# NTS2.net
KiCad netlist of a schematic drawn in EAGLE
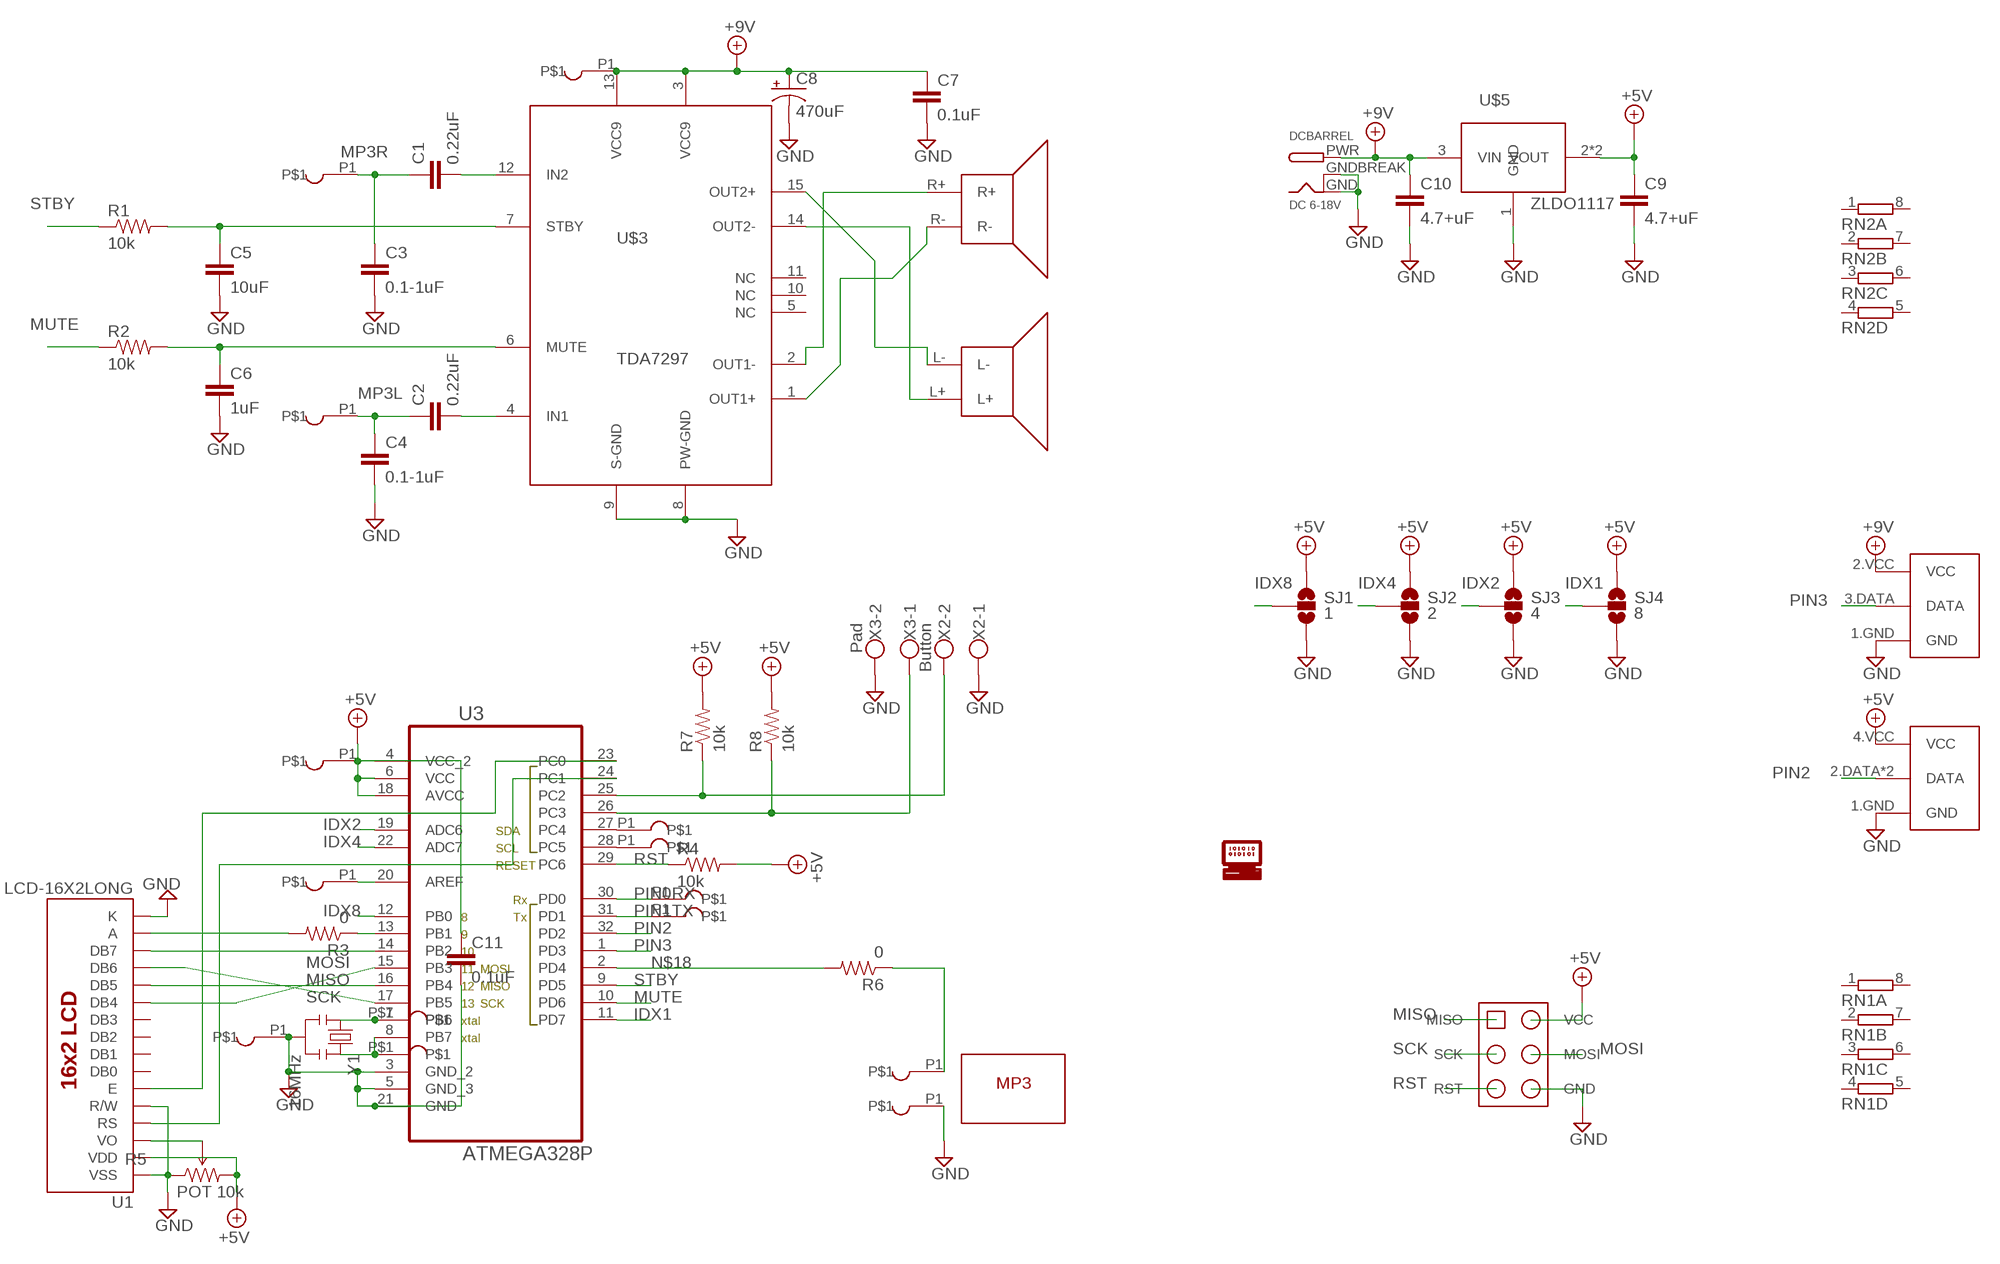
[diagram p0: schematic, sheet 1]

(export (version "E")
  (design (tool "Eeschema 10.0.6"))
  (components
    (comp (ref "AREF")
      (value "AREF")
      (footprint "eagle-import:JMP1")
      (libsource (lib "eagle-import") (part "PROTO-HOLENOSILK"))
    )
    (comp (ref "C1")
      (value "0.22uF")
      (footprint "eagle-import:0805-XL")
      (libsource (lib "eagle-import") (part "CAP0805-XL"))
    )
    (comp (ref "C2")
      (value "0.22uF")
      (footprint "eagle-import:0805-XL")
      (libsource (lib "eagle-import") (part "CAP0805-XL"))
    )
    (comp (ref "C3")
      (value "0.1-1uF")
      (footprint "eagle-import:0805-XL")
      (libsource (lib "eagle-import") (part "CAP0805-XL"))
    )
    (comp (ref "C4")
      (value "0.1-1uF")
      (footprint "eagle-import:0805-XL")
      (libsource (lib "eagle-import") (part "CAP0805-XL"))
    )
    (comp (ref "C5")
      (value "10uF")
      (footprint "eagle-import:0805-XL")
      (libsource (lib "eagle-import") (part "CAP0805-XL"))
    )
    (comp (ref "C6")
      (value "1uF")
      (footprint "eagle-import:0805-XL")
      (libsource (lib "eagle-import") (part "CAP0805-XL"))
    )
    (comp (ref "C7")
      (value "0.1uF")
      (footprint "eagle-import:0805-XL")
      (libsource (lib "eagle-import") (part "CAP0805-XL"))
    )
    (comp (ref "C8")
      (value "470uF")
      (footprint "eagle-import:CAP-PTH-200-POL-HOR-R-600")
      (libsource (lib "eagle-import") (part "CAP_POLHORR"))
    )
    (comp (ref "C9")
      (value "4.7+uF")
      (footprint "eagle-import:1206")
      (libsource (lib "eagle-import") (part "CAP1206"))
    )
    (comp (ref "C10")
      (value "4.7+uF")
      (footprint "eagle-import:0805-XL")
      (libsource (lib "eagle-import") (part "CAP0805-XL"))
    )
    (comp (ref "C11")
      (value "0.1uF")
      (footprint "eagle-import:0805-XL")
      (libsource (lib "eagle-import") (part "CAP0805-XL"))
    )
    (comp (ref "DCBARREL")
      (value "DC 6-18V")
      (footprint "eagle-import:DCJACK_2MM_PTH")
      (libsource (lib "eagle-import") (part "DCBARRELPTH"))
    )
    (comp (ref "GND")
      (value "GND")
      (footprint "eagle-import:JMP1")
      (libsource (lib "eagle-import") (part "PROTO-HOLENOSILK"))
    )
    (comp (ref "MP3+")
      (value "M+")
      (footprint "eagle-import:JMP1-RECT")
      (libsource (lib "eagle-import") (part "PROTO-HOLESILK-RECT"))
    )
    (comp (ref "MP3-")
      (value "M-")
      (footprint "eagle-import:JMP1-RECT")
      (libsource (lib "eagle-import") (part "PROTO-HOLESILK-RECT"))
    )
    (comp (ref "MP3-L")
      (value "L")
      (footprint "eagle-import:JMP1-RECT")
      (libsource (lib "eagle-import") (part "PROTO-HOLESILK-RECT"))
    )
    (comp (ref "MP3-R")
      (value "R")
      (footprint "eagle-import:JMP1-RECT")
      (libsource (lib "eagle-import") (part "PROTO-HOLESILK-RECT"))
    )
    (comp (ref "PB6")
      (value "PB6")
      (footprint "eagle-import:JMP1-SMD-100")
      (libsource (lib "eagle-import") (part "PROTO-HOLESMD100"))
    )
    (comp (ref "PB7")
      (value "PB7")
      (footprint "eagle-import:JMP1-SMD-100")
      (libsource (lib "eagle-import") (part "PROTO-HOLESMD100"))
    )
    (comp (ref "PC4")
      (value "A4")
      (footprint "eagle-import:JMP1")
      (libsource (lib "eagle-import") (part "PROTO-HOLENOSILK"))
    )
    (comp (ref "PC5")
      (value "A5")
      (footprint "eagle-import:JMP1")
      (libsource (lib "eagle-import") (part "PROTO-HOLENOSILK"))
    )
    (comp (ref "PD0")
      (value "Rx")
      (footprint "eagle-import:JMP1")
      (libsource (lib "eagle-import") (part "PROTO-HOLENOSILK"))
    )
    (comp (ref "PD1")
      (value "Tx")
      (footprint "eagle-import:JMP1")
      (libsource (lib "eagle-import") (part "PROTO-HOLENOSILK"))
    )
    (comp (ref "R1")
      (value "10k")
      (footprint "eagle-import:0805-XL")
      (libsource (lib "eagle-import") (part "RESISTOR0805-XL"))
    )
    (comp (ref "R2")
      (value "10k")
      (footprint "eagle-import:0805-XL")
      (libsource (lib "eagle-import") (part "RESISTOR0805-XL"))
    )
    (comp (ref "R3")
      (value "0")
      (footprint "eagle-import:1206")
      (libsource (lib "eagle-import") (part "RESISTOR1206"))
    )
    (comp (ref "R4")
      (value "10k")
      (footprint "eagle-import:0805-XL")
      (libsource (lib "eagle-import") (part "RESISTOR0805-XL"))
    )
    (comp (ref "R5")
      (value "POT 10k")
      (footprint "eagle-import:TRIM_POT_PTH")
      (libsource (lib "eagle-import") (part "TRIMPOTPTH"))
    )
    (comp (ref "R6")
      (value "0")
      (footprint "eagle-import:1206")
      (libsource (lib "eagle-import") (part "RESISTOR1206"))
    )
    (comp (ref "R7")
      (value "10k")
      (footprint "eagle-import:0805-XL")
      (libsource (lib "eagle-import") (part "RESISTOR0805-XL"))
    )
    (comp (ref "R8")
      (value "10k")
      (footprint "eagle-import:0805-XL")
      (libsource (lib "eagle-import") (part "RESISTOR0805-XL"))
    )
    (comp (ref "RN1")
      (value "4R-NCAT16")
      (footprint "eagle-import:CAT16")
      (libsource (lib "eagle-import") (part "4R-NCAT16"))
    )
    (comp (ref "RN2")
      (value "4R-N0402ARV341")
      (footprint "eagle-import:4X0402ARV341")
      (libsource (lib "eagle-import") (part "4R-N0402ARV341"))
    )
    (comp (ref "SJ1")
      (value "1")
      (footprint "eagle-import:SJ_2_BIN-PTH")
      (libsource (lib "eagle-import") (part "JUMPER_2WAYBIN-PTH"))
    )
    (comp (ref "SJ2")
      (value "2")
      (footprint "eagle-import:SJ_2_BIN-PTH")
      (libsource (lib "eagle-import") (part "JUMPER_2WAYBIN-PTH"))
    )
    (comp (ref "SJ3")
      (value "4")
      (footprint "eagle-import:SJ_2_BIN-PTH")
      (libsource (lib "eagle-import") (part "JUMPER_2WAYBIN-PTH"))
    )
    (comp (ref "SJ4")
      (value "8")
      (footprint "eagle-import:SJ_2_BIN-PTH")
      (libsource (lib "eagle-import") (part "JUMPER_2WAYBIN-PTH"))
    )
    (comp (ref "U$1")
      (value "OUTLINE-MP3-MDM")
      (footprint "eagle-import:OUTLINE-MP3-MDM")
      (libsource (lib "eagle-import") (part "OUTLINE-MP3-MDM"))
    )
    (comp (ref "U$2")
      (value "HEAD-2X3-ISPISP6NLL")
      (footprint "eagle-import:HEADER2X3-PTH-NOLABEL-LONG")
      (libsource (lib "eagle-import") (part "HEAD-2X3-ISPISP6NLL"))
    )
    (comp (ref "U$3")
      (value "TDA7297")
      (footprint "eagle-import:TDA7297")
      (libsource (lib "eagle-import") (part "TDA7297-SINK"))
    )
    (comp (ref "U$4")
      (value "SPEAKERSPTH")
      (footprint "eagle-import:SPEAKER-5105")
      (libsource (lib "eagle-import") (part "SPEAKERSPTH"))
    )
    (comp (ref "U$5")
      (value "ZLDO1117")
      (footprint "eagle-import:SOT223-3-L")
      (libsource (lib "eagle-import") (part "VREGZLDO1117"))
    )
    (comp (ref "U$6")
      (value "RF-TRANSMITTER")
      (footprint "eagle-import:RF-TRANSMIT")
      (libsource (lib "eagle-import") (part "RF-TRANSMITTER"))
    )
    (comp (ref "U$7")
      (value "RF-RECEIVER")
      (footprint "eagle-import:RF-RECEIVER")
      (libsource (lib "eagle-import") (part "RF-RECEIVER"))
    )
    (comp (ref "U$8")
      (value "LOGO_HM512")
      (footprint "eagle-import:LOGO_HM_512")
      (libsource (lib "eagle-import") (part "LOGO_HM512"))
    )
    (comp (ref "U1")
      (value "LCD-16X2LONG")
      (footprint "eagle-import:LCD-16X2-LONG")
      (libsource (lib "eagle-import") (part "LCD-16X2LONG"))
    )
    (comp (ref "U3")
      (value "ATMEGA328P")
      (footprint "eagle-import:QFP80P900X900X120-32N-LD")
      (libsource (lib "eagle-import") (part "ATMEGA328P-AUQFP-LONG-DIA"))
    )
    (comp (ref "VCC")
      (value "VCC")
      (footprint "eagle-import:JMP1")
      (libsource (lib "eagle-import") (part "PROTO-HOLENOSILK"))
    )
    (comp (ref "VIN")
      (value "Vin")
      (footprint "eagle-import:JMP1")
      (libsource (lib "eagle-import") (part "PROTO-HOLENOSILK"))
    )
    (comp (ref "X2")
      (value "Button")
      (footprint "eagle-import:CON-SCREW2")
      (fields (field (name "MPN") "237-102"))
      (libsource (lib "eagle-import") (part "CON-SCREW2"))
    )
    (comp (ref "X3")
      (value "Pad")
      (footprint "eagle-import:CON-SCREW2")
      (fields (field (name "MPN") "237-102"))
      (libsource (lib "eagle-import") (part "CON-SCREW2"))
    )
    (comp (ref "Y1")
      (value "16MHz")
      (footprint "eagle-import:SMD-RESONATOR-320-130-PRQC")
      (libsource (lib "eagle-import") (part "RESONATOR8MHZ"))
    )
  )
  (nets
    (net (code "1") (name "+5V") (class "Default")
      (node (ref "C11") (pin "1") (pinfunction "1_1") (pintype "passive"))
      (node (ref "C9") (pin "1") (pinfunction "1_1") (pintype "passive"))
      (node (ref "R4") (pin "2") (pinfunction "2_2") (pintype "passive"))
      (node (ref "R5") (pin "3") (pinfunction "CW_3") (pintype "passive"))
      (node (ref "R7") (pin "2") (pinfunction "2_2") (pintype "passive"))
      (node (ref "R8") (pin "2") (pinfunction "2_2") (pintype "passive"))
      (node (ref "SJ1") (pin "1") (pinfunction "1_1") (pintype "passive"))
      (node (ref "SJ2") (pin "1") (pinfunction "1_1") (pintype "passive"))
      (node (ref "SJ3") (pin "1") (pinfunction "1_1") (pintype "passive"))
      (node (ref "SJ4") (pin "1") (pinfunction "1_1") (pintype "passive"))
      (node (ref "U$2") (pin "VCC") (pinfunction "VCC_VCC") (pintype "bidirectional"))
      (node (ref "U$5") (pin "2") (pinfunction "VOUT_2") (pintype "power_in"))
      (node (ref "U$5") (pin "4") (pinfunction "VOUT_4") (pintype "power_in"))
      (node (ref "U$7") (pin "4.VCC") (pinfunction "VCC_4.VCC") (pintype "power_in"))
      (node (ref "U1") (pin "2") (pinfunction "VDD_2") (pintype "power_in"))
      (node (ref "U3") (pin "18") (pinfunction "AVCC_18") (pintype "power_in"))
      (node (ref "U3") (pin "4") (pinfunction "VCC_2_4") (pintype "power_in"))
      (node (ref "U3") (pin "6") (pinfunction "VCC_6") (pintype "power_in"))
      (node (ref "VCC") (pin "P1") (pinfunction "P$1_P1") (pintype "bidirectional"))
    )
    (net (code "2") (name "+9V") (class "Default")
      (node (ref "C10") (pin "1") (pinfunction "1_1") (pintype "passive"))
      (node (ref "C7") (pin "1") (pinfunction "1_1") (pintype "passive"))
      (node (ref "C8") (pin "2+") (pinfunction "+_2+") (pintype "passive"))
      (node (ref "DCBARREL") (pin "PWR") (pinfunction "PWR_PWR") (pintype "power_in"))
      (node (ref "U$3") (pin "13") (pinfunction "VCC9_13") (pintype "power_in"))
      (node (ref "U$3") (pin "3") (pinfunction "VCC9_3") (pintype "power_in"))
      (node (ref "U$5") (pin "3") (pinfunction "VIN_3") (pintype "power_in"))
      (node (ref "U$6") (pin "2.VCC") (pinfunction "VCC_2.VCC") (pintype "power_in"))
      (node (ref "VIN") (pin "P1") (pinfunction "P$1_P1") (pintype "bidirectional"))
    )
    (net (code "3") (name "/IDX1") (class "Default")
      (node (ref "SJ4") (pin "2") (pinfunction "2.C_2") (pintype "passive"))
      (node (ref "U3") (pin "11") (pinfunction "PD7_11") (pintype "bidirectional"))
    )
    (net (code "4") (name "/IDX2") (class "Default")
      (node (ref "SJ3") (pin "2") (pinfunction "2.C_2") (pintype "passive"))
      (node (ref "U3") (pin "19") (pinfunction "ADC6_19") (pintype "input"))
    )
    (net (code "5") (name "/IDX4") (class "Default")
      (node (ref "SJ2") (pin "2") (pinfunction "2.C_2") (pintype "passive"))
      (node (ref "U3") (pin "22") (pinfunction "ADC7_22") (pintype "input"))
    )
    (net (code "6") (name "/IDX8") (class "Default")
      (node (ref "SJ1") (pin "2") (pinfunction "2.C_2") (pintype "passive"))
      (node (ref "U3") (pin "12") (pinfunction "PB0_12") (pintype "bidirectional"))
    )
    (net (code "7") (name "/MISO") (class "Default")
      (node (ref "U$2") (pin "MISO") (pinfunction "MISO_MISO") (pintype "bidirectional"))
      (node (ref "U1") (pin "12") (pinfunction "DB5_12") (pintype "bidirectional"))
      (node (ref "U3") (pin "16") (pinfunction "PB4_16") (pintype "bidirectional"))
    )
    (net (code "8") (name "/MOSI") (class "Default")
      (node (ref "U$2") (pin "MOSI") (pinfunction "MOSI_MOSI") (pintype "bidirectional"))
      (node (ref "U1") (pin "11") (pinfunction "DB4_11") (pintype "bidirectional"))
      (node (ref "U3") (pin "15") (pinfunction "PB3_15") (pintype "bidirectional"))
    )
    (net (code "9") (name "/MP3L") (class "Default")
      (node (ref "C2") (pin "1") (pinfunction "1_1") (pintype "passive"))
      (node (ref "C4") (pin "1") (pinfunction "1_1") (pintype "passive"))
      (node (ref "MP3-L") (pin "P1") (pinfunction "P$1_P1") (pintype "bidirectional"))
    )
    (net (code "10") (name "/MP3R") (class "Default")
      (node (ref "C1") (pin "1") (pinfunction "1_1") (pintype "passive"))
      (node (ref "C3") (pin "1") (pinfunction "1_1") (pintype "passive"))
      (node (ref "MP3-R") (pin "P1") (pinfunction "P$1_P1") (pintype "bidirectional"))
    )
    (net (code "11") (name "/MUTE") (class "Default")
      (node (ref "R2") (pin "1") (pinfunction "1_1") (pintype "passive"))
      (node (ref "U3") (pin "10") (pinfunction "PD6_10") (pintype "bidirectional"))
    )
    (net (code "12") (name "/N$18") (class "Default")
      (node (ref "R6") (pin "2") (pinfunction "2_2") (pintype "passive"))
      (node (ref "U3") (pin "2") (pinfunction "PD4_2") (pintype "bidirectional"))
    )
    (net (code "13") (name "/PIN0RX") (class "Default")
      (node (ref "PD0") (pin "P1") (pinfunction "P$1_P1") (pintype "bidirectional"))
      (node (ref "U3") (pin "30") (pinfunction "PD0_30") (pintype "bidirectional"))
    )
    (net (code "14") (name "/PIN1TX") (class "Default")
      (node (ref "PD1") (pin "P1") (pinfunction "P$1_P1") (pintype "bidirectional"))
      (node (ref "U3") (pin "31") (pinfunction "PD1_31") (pintype "bidirectional"))
    )
    (net (code "15") (name "/PIN2") (class "Default")
      (node (ref "U$7") (pin "2.DATA") (pinfunction "DATA_2.DATA") (pintype "output"))
      (node (ref "U$7") (pin "3.DATA") (pinfunction "DATA_3.DATA") (pintype "output"))
      (node (ref "U3") (pin "32") (pinfunction "PD2_32") (pintype "bidirectional"))
    )
    (net (code "16") (name "/PIN3") (class "Default")
      (node (ref "U$6") (pin "3.DATA") (pinfunction "DATA_3.DATA") (pintype "input"))
      (node (ref "U3") (pin "1") (pinfunction "PD3_1") (pintype "bidirectional"))
    )
    (net (code "17") (name "/RST") (class "Default")
      (node (ref "R4") (pin "1") (pinfunction "1_1") (pintype "passive"))
      (node (ref "U$2") (pin "RST") (pinfunction "RST_RST") (pintype "bidirectional"))
      (node (ref "U3") (pin "29") (pinfunction "PC6_29") (pintype "bidirectional"))
    )
    (net (code "18") (name "/SCK") (class "Default")
      (node (ref "U$2") (pin "SCK") (pinfunction "SCK_SCK") (pintype "bidirectional"))
      (node (ref "U1") (pin "13") (pinfunction "DB6_13") (pintype "bidirectional"))
      (node (ref "U3") (pin "17") (pinfunction "PB5_17") (pintype "bidirectional"))
    )
    (net (code "19") (name "/STBY") (class "Default")
      (node (ref "R1") (pin "1") (pinfunction "1_1") (pintype "passive"))
      (node (ref "U3") (pin "9") (pinfunction "PD5_9") (pintype "bidirectional"))
    )
    (net (code "20") (name "GND") (class "Default")
      (node (ref "C10") (pin "2") (pinfunction "2_2") (pintype "passive"))
      (node (ref "C11") (pin "2") (pinfunction "2_2") (pintype "passive"))
      (node (ref "C3") (pin "2") (pinfunction "2_2") (pintype "passive"))
      (node (ref "C4") (pin "2") (pinfunction "2_2") (pintype "passive"))
      (node (ref "C5") (pin "2") (pinfunction "2_2") (pintype "passive"))
      (node (ref "C6") (pin "2") (pinfunction "2_2") (pintype "passive"))
      (node (ref "C7") (pin "2") (pinfunction "2_2") (pintype "passive"))
      (node (ref "C8") (pin "1-") (pinfunction "-_1-") (pintype "passive"))
      (node (ref "C9") (pin "2") (pinfunction "2_2") (pintype "passive"))
      (node (ref "DCBARREL") (pin "GND") (pinfunction "GND_GND") (pintype "power_in"))
      (node (ref "DCBARREL") (pin "GNDBREAK") (pinfunction "GNDBREAK_GNDBREAK") (pintype "power_in"))
      (node (ref "GND") (pin "P1") (pinfunction "P$1_P1") (pintype "bidirectional"))
      (node (ref "MP3-") (pin "P1") (pinfunction "P$1_P1") (pintype "bidirectional"))
      (node (ref "R5") (pin "1") (pinfunction "CCW_1") (pintype "passive"))
      (node (ref "SJ1") (pin "3") (pinfunction "3_3") (pintype "passive"))
      (node (ref "SJ2") (pin "3") (pinfunction "3_3") (pintype "passive"))
      (node (ref "SJ3") (pin "3") (pinfunction "3_3") (pintype "passive"))
      (node (ref "SJ4") (pin "3") (pinfunction "3_3") (pintype "passive"))
      (node (ref "U$2") (pin "GND") (pinfunction "GND_GND") (pintype "bidirectional"))
      (node (ref "U$3") (pin "8") (pinfunction "PW-GND_8") (pintype "power_in"))
      (node (ref "U$3") (pin "9") (pinfunction "S-GND_9") (pintype "power_in"))
      (node (ref "U$5") (pin "1") (pinfunction "GND_1") (pintype "power_in"))
      (node (ref "U$6") (pin "1.GND") (pinfunction "GND_1.GND") (pintype "power_in"))
      (node (ref "U$7") (pin "1.GND") (pinfunction "GND_1.GND") (pintype "power_in"))
      (node (ref "U1") (pin "1") (pinfunction "VSS_1") (pintype "power_in"))
      (node (ref "U1") (pin "16") (pinfunction "K_16") (pintype "power_in"))
      (node (ref "U1") (pin "5") (pinfunction "R/W_5") (pintype "input"))
      (node (ref "U3") (pin "21") (pinfunction "GND_21") (pintype "passive"))
      (node (ref "U3") (pin "3") (pinfunction "GND_2_3") (pintype "passive"))
      (node (ref "U3") (pin "5") (pinfunction "GND_3_5") (pintype "passive"))
      (node (ref "X2") (pin "1") (pinfunction "KL_1") (pintype "passive"))
      (node (ref "X3") (pin "2") (pinfunction "KL_2") (pintype "passive"))
      (node (ref "Y1") (pin "2.GND") (pinfunction "2.GND_2.GND") (pintype "passive"))
    )
    (net (code "21") (name "Net-(AREF-P$1)") (class "Default")
      (node (ref "AREF") (pin "P1") (pinfunction "P$1_P1") (pintype "bidirectional"))
      (node (ref "U3") (pin "20") (pinfunction "AREF_20") (pintype "input"))
    )
    (net (code "22") (name "Net-(MP3+-P$1)") (class "Default")
      (node (ref "MP3+") (pin "P1") (pinfunction "P$1_P1") (pintype "bidirectional"))
      (node (ref "R6") (pin "1") (pinfunction "1_1") (pintype "passive"))
    )
    (net (code "23") (name "Net-(PC4-P$1)") (class "Default")
      (node (ref "PC4") (pin "P1") (pinfunction "P$1_P1") (pintype "bidirectional"))
      (node (ref "U3") (pin "27") (pinfunction "PC4_27") (pintype "bidirectional"))
    )
    (net (code "24") (name "Net-(PC5-P$1)") (class "Default")
      (node (ref "PC5") (pin "P1") (pinfunction "P$1_P1") (pintype "bidirectional"))
      (node (ref "U3") (pin "28") (pinfunction "PC5_28") (pintype "bidirectional"))
    )
    (net (code "25") (name "Net-(R5-WIPER)") (class "Default")
      (node (ref "R5") (pin "2") (pinfunction "WIPER_2") (pintype "passive"))
      (node (ref "U1") (pin "3") (pinfunction "VO_3") (pintype "bidirectional"))
    )
    (net (code "26") (name "Net-(U$3-IN1)") (class "Default")
      (node (ref "C2") (pin "2") (pinfunction "2_2") (pintype "passive"))
      (node (ref "U$3") (pin "4") (pinfunction "IN1_4") (pintype "input"))
    )
    (net (code "27") (name "Net-(U$3-IN2)") (class "Default")
      (node (ref "C1") (pin "2") (pinfunction "2_2") (pintype "passive"))
      (node (ref "U$3") (pin "12") (pinfunction "IN2_12") (pintype "input"))
    )
    (net (code "28") (name "Net-(U$3-MUTE)") (class "Default")
      (node (ref "C6") (pin "1") (pinfunction "1_1") (pintype "passive"))
      (node (ref "R2") (pin "2") (pinfunction "2_2") (pintype "passive"))
      (node (ref "U$3") (pin "6") (pinfunction "MUTE_6") (pintype "input"))
    )
    (net (code "29") (name "Net-(U$3-OUT1+)") (class "Default")
      (node (ref "U$3") (pin "1") (pinfunction "OUT1+_1") (pintype "bidirectional"))
      (node (ref "U$4") (pin "R-") (pinfunction "R-_R-") (pintype "bidirectional"))
    )
    (net (code "30") (name "Net-(U$3-OUT1-)") (class "Default")
      (node (ref "U$3") (pin "2") (pinfunction "OUT1-_2") (pintype "bidirectional"))
      (node (ref "U$4") (pin "R+") (pinfunction "R+_R+") (pintype "bidirectional"))
    )
    (net (code "31") (name "Net-(U$3-OUT2+)") (class "Default")
      (node (ref "U$3") (pin "15") (pinfunction "OUT2+_15") (pintype "bidirectional"))
      (node (ref "U$4") (pin "L-") (pinfunction "L-_L-") (pintype "bidirectional"))
    )
    (net (code "32") (name "Net-(U$3-OUT2-)") (class "Default")
      (node (ref "U$3") (pin "14") (pinfunction "OUT2-_14") (pintype "bidirectional"))
      (node (ref "U$4") (pin "L+") (pinfunction "L+_L+") (pintype "bidirectional"))
    )
    (net (code "33") (name "Net-(U$3-STBY)") (class "Default")
      (node (ref "C5") (pin "1") (pinfunction "1_1") (pintype "passive"))
      (node (ref "R1") (pin "2") (pinfunction "2_2") (pintype "passive"))
      (node (ref "U$3") (pin "7") (pinfunction "STBY_7") (pintype "input"))
    )
    (net (code "34") (name "Net-(U1-A)") (class "Default")
      (node (ref "R3") (pin "2") (pinfunction "2_2") (pintype "passive"))
      (node (ref "U1") (pin "15") (pinfunction "A_15") (pintype "power_in"))
    )
    (net (code "35") (name "Net-(U1-DB7)") (class "Default")
      (node (ref "U1") (pin "14") (pinfunction "DB7_14") (pintype "bidirectional"))
      (node (ref "U3") (pin "14") (pinfunction "PB2_14") (pintype "bidirectional"))
    )
    (net (code "36") (name "Net-(U1-E)") (class "Default")
      (node (ref "U1") (pin "6") (pinfunction "E_6") (pintype "input"))
      (node (ref "U3") (pin "23") (pinfunction "PC0_23") (pintype "bidirectional"))
    )
    (net (code "37") (name "Net-(U1-RS)") (class "Default")
      (node (ref "U1") (pin "4") (pinfunction "RS_4") (pintype "input"))
      (node (ref "U3") (pin "24") (pinfunction "PC1_24") (pintype "bidirectional"))
    )
    (net (code "38") (name "Net-(U3-PB1)") (class "Default")
      (node (ref "R3") (pin "1") (pinfunction "1_1") (pintype "passive"))
      (node (ref "U3") (pin "13") (pinfunction "PB1_13") (pintype "bidirectional"))
    )
    (net (code "39") (name "Net-(U3-PB6)") (class "Default")
      (node (ref "PB6") (pin "P$1") (pinfunction "P$1_P$1") (pintype "bidirectional"))
      (node (ref "U3") (pin "7") (pinfunction "PB6_7") (pintype "bidirectional"))
      (node (ref "Y1") (pin "1") (pinfunction "1_1") (pintype "passive"))
    )
    (net (code "40") (name "Net-(U3-PB7)") (class "Default")
      (node (ref "PB7") (pin "P$1") (pinfunction "P$1_P$1") (pintype "bidirectional"))
      (node (ref "U3") (pin "8") (pinfunction "PB7_8") (pintype "bidirectional"))
      (node (ref "Y1") (pin "3") (pinfunction "3_3") (pintype "passive"))
    )
    (net (code "41") (name "Net-(U3-PC2)") (class "Default")
      (node (ref "R7") (pin "1") (pinfunction "1_1") (pintype "passive"))
      (node (ref "U3") (pin "25") (pinfunction "PC2_25") (pintype "bidirectional"))
      (node (ref "X2") (pin "2") (pinfunction "KL_2") (pintype "passive"))
    )
    (net (code "42") (name "Net-(U3-PC3)") (class "Default")
      (node (ref "R8") (pin "1") (pinfunction "1_1") (pintype "passive"))
      (node (ref "U3") (pin "26") (pinfunction "PC3_26") (pintype "bidirectional"))
      (node (ref "X3") (pin "1") (pinfunction "KL_1") (pintype "passive"))
    )
    (net (code "43") (name "unconnected-(RN1-Pad1)") (class "Default")
      (node (ref "RN1") (pin "1") (pinfunction "1_1") (pintype "passive"))
    )
    (net (code "44") (name "unconnected-(RN1A-2-Pad8)") (class "Default")
      (node (ref "RN1") (pin "8") (pinfunction "2_8") (pintype "passive"))
    )
    (net (code "45") (name "unconnected-(RN1B-1-Pad2)") (class "Default")
      (node (ref "RN1") (pin "2") (pinfunction "1_2") (pintype "passive"))
    )
    (net (code "46") (name "unconnected-(RN1B-2-Pad7)") (class "Default")
      (node (ref "RN1") (pin "7") (pinfunction "2_7") (pintype "passive"))
    )
    (net (code "47") (name "unconnected-(RN1C-1-Pad3)") (class "Default")
      (node (ref "RN1") (pin "3") (pinfunction "1_3") (pintype "passive"))
    )
    (net (code "48") (name "unconnected-(RN1C-2-Pad6)") (class "Default")
      (node (ref "RN1") (pin "6") (pinfunction "2_6") (pintype "passive"))
    )
    (net (code "49") (name "unconnected-(RN1D-1-Pad4)") (class "Default")
      (node (ref "RN1") (pin "4") (pinfunction "1_4") (pintype "passive"))
    )
    (net (code "50") (name "unconnected-(RN1D-2-Pad5)") (class "Default")
      (node (ref "RN1") (pin "5") (pinfunction "2_5") (pintype "passive"))
    )
    (net (code "51") (name "unconnected-(RN2-Pad1)") (class "Default")
      (node (ref "RN2") (pin "1") (pinfunction "1_1") (pintype "passive"))
    )
    (net (code "52") (name "unconnected-(RN2A-2-Pad8)") (class "Default")
      (node (ref "RN2") (pin "8") (pinfunction "2_8") (pintype "passive"))
    )
    (net (code "53") (name "unconnected-(RN2B-1-Pad2)") (class "Default")
      (node (ref "RN2") (pin "2") (pinfunction "1_2") (pintype "passive"))
    )
    (net (code "54") (name "unconnected-(RN2B-2-Pad7)") (class "Default")
      (node (ref "RN2") (pin "7") (pinfunction "2_7") (pintype "passive"))
    )
    (net (code "55") (name "unconnected-(RN2C-1-Pad3)") (class "Default")
      (node (ref "RN2") (pin "3") (pinfunction "1_3") (pintype "passive"))
    )
    (net (code "56") (name "unconnected-(RN2C-2-Pad6)") (class "Default")
      (node (ref "RN2") (pin "6") (pinfunction "2_6") (pintype "passive"))
    )
    (net (code "57") (name "unconnected-(RN2D-1-Pad4)") (class "Default")
      (node (ref "RN2") (pin "4") (pinfunction "1_4") (pintype "passive"))
    )
    (net (code "58") (name "unconnected-(RN2D-2-Pad5)") (class "Default")
      (node (ref "RN2") (pin "5") (pinfunction "2_5") (pintype "passive"))
    )
    (net (code "59") (name "unconnected-(U$3-NC-Pad5)") (class "Default")
      (node (ref "U$3") (pin "5") (pinfunction "NC_5") (pintype "no_connect"))
    )
    (net (code "60") (name "unconnected-(U$3-NC-Pad10)") (class "Default")
      (node (ref "U$3") (pin "10") (pinfunction "NC_10") (pintype "no_connect"))
    )
    (net (code "61") (name "unconnected-(U$3-NC-Pad11)") (class "Default")
      (node (ref "U$3") (pin "11") (pinfunction "NC_11") (pintype "no_connect"))
    )
    (net (code "62") (name "unconnected-(U1-DB0-Pad7)") (class "Default")
      (node (ref "U1") (pin "7") (pinfunction "DB0_7") (pintype "bidirectional"))
    )
    (net (code "63") (name "unconnected-(U1-DB1-Pad8)") (class "Default")
      (node (ref "U1") (pin "8") (pinfunction "DB1_8") (pintype "bidirectional"))
    )
    (net (code "64") (name "unconnected-(U1-DB2-Pad9)") (class "Default")
      (node (ref "U1") (pin "9") (pinfunction "DB2_9") (pintype "bidirectional"))
    )
    (net (code "65") (name "unconnected-(U1-DB3-Pad10)") (class "Default")
      (node (ref "U1") (pin "10") (pinfunction "DB3_10") (pintype "bidirectional"))
    )
  )
)
